# CN3791_solar.net
KiCad netlist of a schematic drawn in Altium Designer
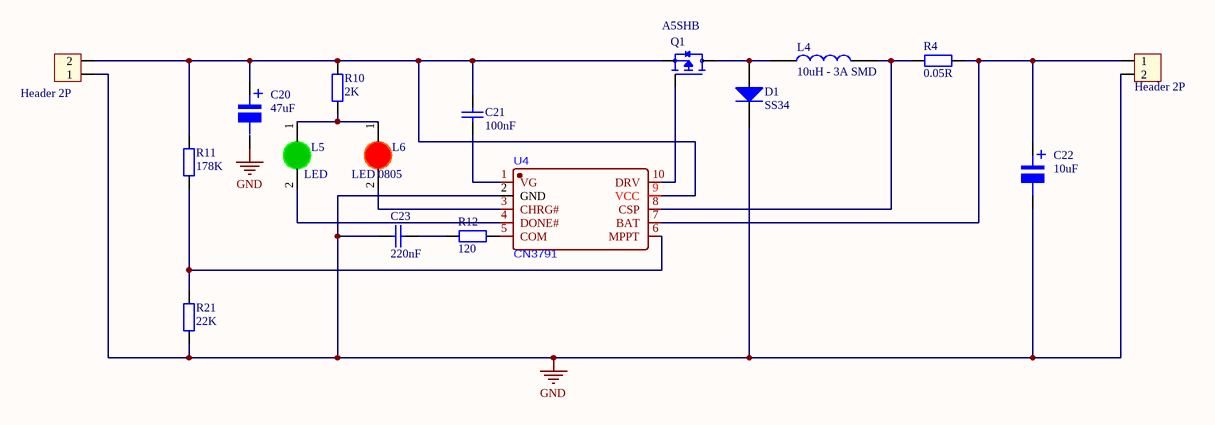
[diagram p0: CN3791_solar.SchDoc]

(export (version "E")
  (design (tool "Eeschema 10.0.6"))
  (components
    (comp (ref "C20")
      (value "47uF")
      (footprint "tu nhom 5 (c)")
      (description "Dán")
      (libsource (lib "Altium_Lib_by_KhueNguyenCreator") (part "Tu Nhom 10uF 20V"))
    )
    (comp (ref "C21")
      (value "100nF")
      (footprint "tu 0805")
      (description "Dán")
      (libsource (lib "THU VIEN SCH") (part "Tu 0805 33nF 50V 20%"))
    )
    (comp (ref "C22")
      (value "10uF")
      (footprint "tu nhom 5 (c)")
      (description "Dán")
      (libsource (lib "Altium_Lib_by_KhueNguyenCreator") (part "Tu Nhom 10uF 20V"))
    )
    (comp (ref "C23")
      (value "220nF")
      (footprint "tu 0805")
      (description "Dán")
      (libsource (lib "THU VIEN SCH") (part "Tu 0805 33nF 50V 20%"))
    )
    (comp (ref "D1")
      (value "SS34")
      (footprint "DIODE SMA")
      (description "Dán")
      (libsource (lib "Altium_Lib_by_KhueNguyenCreator") (part "Diode SS34 ( 1N5822 )"))
    )
    (comp (ref "H2")
      (value "Header 2P")
      (footprint "XH2.54M-2")
      (description "Cắm")
      (libsource (lib "") (part "Header 2P 2.54 Duc Thang_1"))
    )
    (comp (ref "H3")
      (value "Header 2P")
      (footprint "XH2.54M-2")
      (description "Cắm")
      (libsource (lib "Altium_Lib_by_KhueNguyenCreator") (part "Header 2P 2.54 Duc Thang"))
    )
    (comp (ref "L4")
      (value "10uH - 3A SMD")
      (footprint "CUON CAM SMD 0530")
      (description "Dán")
      (libsource (lib "Altium_Lib_by_KhueNguyenCreator") (part "CUON CAM 100uH SMD"))
    )
    (comp (ref "L5")
      (value "LED")
      (footprint "LED-0805-Green")
      (description "Dán")
      (libsource (lib "Altium_Lib_by_KhueNguyenCreator") (part "LED 0805 Xanh La"))
    )
    (comp (ref "L6")
      (value "LED 0805")
      (footprint "LED-0805-Red")
      (description "Dán")
      (libsource (lib "Altium_Lib_by_KhueNguyenCreator") (part "LED 0805 Do"))
    )
    (comp (ref "Q1")
      (value "A5SHB")
      (footprint "TRANS_MMFTP2319")
      (description "MOSFET, SOT-23, P, -40V, -4.2A, 0.08â„¦, 150Â°C")
      (fields (field (name "MF") "Diotec Semiconductor") (field (name "MP") "MMFTP2319"))
      (libsource (lib "MMFTP2319") (part "MMFTP2319"))
    )
    (comp (ref "R4")
      (value "0.05R")
      (footprint "tro smd 2512")
      (description "Dán")
      (libsource (lib "Altium_Lib_by_KhueNguyenCreator") (part "Tro 2512 5% 0.5R"))
    )
    (comp (ref "R10")
      (value "2K")
      (footprint "tro smd 0805")
      (description "Dán")
      (libsource (lib "THU VIEN SCH") (part "Tro 0805 1% 1k"))
    )
    (comp (ref "R11")
      (value "178K")
      (footprint "tro smd 0805")
      (description "Dán")
      (libsource (lib "THU VIEN SCH") (part "Tro 0805 1% 1k"))
    )
    (comp (ref "R12")
      (value "120")
      (footprint "tro smd 0805")
      (description "Dán")
      (libsource (lib "THU VIEN SCH") (part "Tro 0805 1% 1k"))
    )
    (comp (ref "R21")
      (value "22K")
      (footprint "tro smd 0805")
      (description "Dán")
      (libsource (lib "THU VIEN SCH") (part "Tro 0805 1% 1k"))
    )
    (comp (ref "U4")
      (value "CN3791")
      (footprint "SSOP-10_L4.9-W3.9-P1.00-LS6.0-BL")
      (libsource (lib "CN3791") (part "CN3791"))
    )
  )
  (nets
    (net (code "1") (name "GND") (class "Default")
      (node (ref "C20") (pin "2") (pinfunction "2_2") (pintype "passive"))
      (node (ref "C22") (pin "2") (pinfunction "2_2") (pintype "passive"))
      (node (ref "C23") (pin "2") (pinfunction "2_2") (pintype "passive"))
      (node (ref "D1") (pin "2") (pinfunction "K_2") (pintype "passive"))
      (node (ref "H2") (pin "1") (pinfunction "1_1") (pintype "passive"))
      (node (ref "H3") (pin "2") (pinfunction "2_2") (pintype "passive"))
      (node (ref "R21") (pin "1") (pinfunction "1_1") (pintype "passive"))
      (node (ref "U4") (pin "2") (pinfunction "GND_2") (pintype "passive"))
    )
    (net (code "2") (name "Net-(C23-Pad1)") (class "Default")
      (node (ref "C23") (pin "1") (pinfunction "1_1") (pintype "passive"))
      (node (ref "R12") (pin "1") (pinfunction "1_1") (pintype "passive"))
    )
    (net (code "3") (name "Net-(D1-A)") (class "Default")
      (node (ref "D1") (pin "1") (pinfunction "A_1") (pintype "passive"))
      (node (ref "L4") (pin "1") (pinfunction "1_1") (pintype "passive"))
      (node (ref "Q1") (pin "3") (pinfunction "D_3") (pintype "passive"))
    )
    (net (code "4") (name "Net-(L5-A)") (class "Default")
      (node (ref "L5") (pin "1") (pinfunction "A_1") (pintype "passive"))
      (node (ref "L6") (pin "1") (pinfunction "A_1") (pintype "passive"))
      (node (ref "R10") (pin "1") (pinfunction "1_1") (pintype "passive"))
    )
    (net (code "5") (name "Net-(L5-K)") (class "Default")
      (node (ref "L5") (pin "2") (pinfunction "K_2") (pintype "passive"))
      (node (ref "U4") (pin "4") (pinfunction "DONE#_4") (pintype "passive"))
    )
    (net (code "6") (name "Net-(L6-K)") (class "Default")
      (node (ref "L6") (pin "2") (pinfunction "K_2") (pintype "passive"))
      (node (ref "U4") (pin "3") (pinfunction "CHRG#_3") (pintype "passive"))
    )
    (net (code "7") (name "Net-(Q1-G)") (class "Default")
      (node (ref "Q1") (pin "1") (pinfunction "G_1") (pintype "passive"))
      (node (ref "U4") (pin "10") (pinfunction "DRV_10") (pintype "passive"))
    )
    (net (code "8") (name "Net-(Q1-S)") (class "Default")
      (node (ref "C20") (pin "1") (pinfunction "1_1") (pintype "passive"))
      (node (ref "C21") (pin "1") (pinfunction "1_1") (pintype "passive"))
      (node (ref "H2") (pin "2") (pinfunction "2_2") (pintype "passive"))
      (node (ref "Q1") (pin "2") (pinfunction "S_2") (pintype "passive"))
      (node (ref "R10") (pin "2") (pinfunction "2_2") (pintype "passive"))
      (node (ref "R11") (pin "2") (pinfunction "2_2") (pintype "passive"))
      (node (ref "U4") (pin "9") (pinfunction "VCC_9") (pintype "passive"))
    )
    (net (code "9") (name "Net-(U4-BAT)") (class "Default")
      (node (ref "C22") (pin "1") (pinfunction "1_1") (pintype "passive"))
      (node (ref "H3") (pin "1") (pinfunction "1_1") (pintype "passive"))
      (node (ref "R4") (pin "2") (pinfunction "2_2") (pintype "passive"))
      (node (ref "U4") (pin "7") (pinfunction "BAT_7") (pintype "passive"))
    )
    (net (code "10") (name "Net-(U4-COM)") (class "Default")
      (node (ref "R12") (pin "2") (pinfunction "2_2") (pintype "passive"))
      (node (ref "U4") (pin "5") (pinfunction "COM_5") (pintype "passive"))
    )
    (net (code "11") (name "Net-(U4-CSP)") (class "Default")
      (node (ref "L4") (pin "2") (pinfunction "2_2") (pintype "passive"))
      (node (ref "R4") (pin "1") (pinfunction "1_1") (pintype "passive"))
      (node (ref "U4") (pin "8") (pinfunction "CSP_8") (pintype "passive"))
    )
    (net (code "12") (name "Net-(U4-MPPT)") (class "Default")
      (node (ref "R11") (pin "1") (pinfunction "1_1") (pintype "passive"))
      (node (ref "R21") (pin "2") (pinfunction "2_2") (pintype "passive"))
      (node (ref "U4") (pin "6") (pinfunction "MPPT_6") (pintype "passive"))
    )
    (net (code "13") (name "Net-(U4-VG)") (class "Default")
      (node (ref "C21") (pin "2") (pinfunction "2_2") (pintype "passive"))
      (node (ref "U4") (pin "1") (pinfunction "VG_1") (pintype "passive"))
    )
  )
)
